# IRComms.net
KiCad netlist of a schematic drawn in Altium Designer
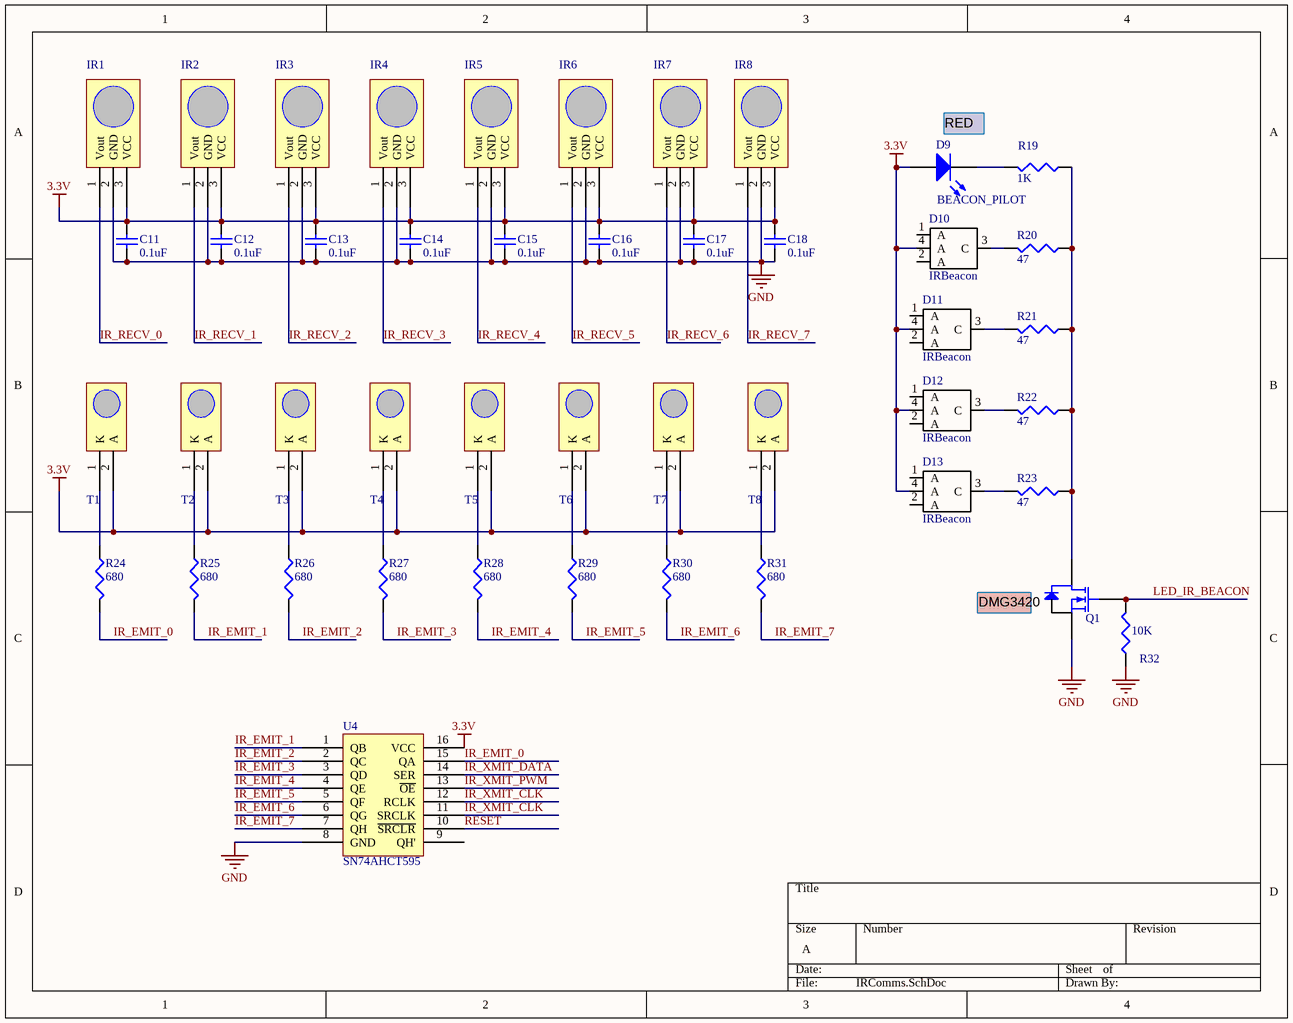
[diagram p0: IRComms.SchDoc]

(export (version "E")
  (design (tool "Eeschema 10.0.6"))
  (components
    (comp (ref "C11")
      (value "0.1uF")
      (footprint "CAPC1005L")
      (description "Capacitor (Semiconductor SIM Model)")
      (fields (field (name "Comment") "Cap Semi") (field (name "PUBLISHER") "Altium Limited"))
      (libsource (lib "Miscellaneous Devices") (part "Cap Semi"))
    )
    (comp (ref "C12")
      (value "0.1uF")
      (footprint "CAPC1005L")
      (description "Capacitor (Semiconductor SIM Model)")
      (fields (field (name "Comment") "Cap Semi") (field (name "PUBLISHER") "Altium Limited"))
      (libsource (lib "Miscellaneous Devices") (part "Cap Semi"))
    )
    (comp (ref "C13")
      (value "0.1uF")
      (footprint "CAPC1005L")
      (description "Capacitor (Semiconductor SIM Model)")
      (fields (field (name "Comment") "Cap Semi") (field (name "PUBLISHER") "Altium Limited"))
      (libsource (lib "Miscellaneous Devices") (part "Cap Semi"))
    )
    (comp (ref "C14")
      (value "0.1uF")
      (footprint "CAPC1005L")
      (description "Capacitor (Semiconductor SIM Model)")
      (fields (field (name "Comment") "Cap Semi") (field (name "PUBLISHER") "Altium Limited"))
      (libsource (lib "Miscellaneous Devices") (part "Cap Semi"))
    )
    (comp (ref "C15")
      (value "0.1uF")
      (footprint "CAPC1005L")
      (description "Capacitor (Semiconductor SIM Model)")
      (fields (field (name "Comment") "Cap Semi") (field (name "PUBLISHER") "Altium Limited"))
      (libsource (lib "Miscellaneous Devices") (part "Cap Semi"))
    )
    (comp (ref "C16")
      (value "0.1uF")
      (footprint "CAPC1005L")
      (description "Capacitor (Semiconductor SIM Model)")
      (fields (field (name "Comment") "Cap Semi") (field (name "PUBLISHER") "Altium Limited"))
      (libsource (lib "Miscellaneous Devices") (part "Cap Semi"))
    )
    (comp (ref "C17")
      (value "0.1uF")
      (footprint "CAPC1005L")
      (description "Capacitor (Semiconductor SIM Model)")
      (fields (field (name "Comment") "Cap Semi") (field (name "PUBLISHER") "Altium Limited"))
      (libsource (lib "Miscellaneous Devices") (part "Cap Semi"))
    )
    (comp (ref "C18")
      (value "0.1uF")
      (footprint "CAPC1005L")
      (description "Capacitor (Semiconductor SIM Model)")
      (fields (field (name "Comment") "Cap Semi") (field (name "PUBLISHER") "Altium Limited"))
      (libsource (lib "Miscellaneous Devices") (part "Cap Semi"))
    )
    (comp (ref "D9")
      (value "BEACON_PILOT")
      (footprint "SurfaceMount(603)")
      (libsource (lib "mrone") (part "LED"))
    )
    (comp (ref "D10") (value "IRBeacon") (footprint "IRBeacon") (libsource (lib "mrone") (part "IRBeacon")))
    (comp (ref "D11") (value "IRBeacon") (footprint "IRBeacon") (libsource (lib "mrone") (part "IRBeacon")))
    (comp (ref "D12") (value "IRBeacon") (footprint "IRBeacon") (libsource (lib "mrone") (part "IRBeacon")))
    (comp (ref "D13") (value "IRBeacon") (footprint "IRBeacon") (libsource (lib "mrone") (part "IRBeacon")))
    (comp (ref "IR1")
      (value "GP1UX31QS")
      (footprint "GP1UX31QS")
      (libsource (lib "mrone") (part "GP1UX31QS"))
    )
    (comp (ref "IR2")
      (value "GP1UX31QS")
      (footprint "GP1UX31QS")
      (libsource (lib "mrone") (part "GP1UX31QS"))
    )
    (comp (ref "IR3")
      (value "GP1UX31QS")
      (footprint "GP1UX31QS")
      (libsource (lib "mrone") (part "GP1UX31QS"))
    )
    (comp (ref "IR4")
      (value "GP1UX31QS")
      (footprint "GP1UX31QS")
      (libsource (lib "mrone") (part "GP1UX31QS"))
    )
    (comp (ref "IR5")
      (value "GP1UX31QS")
      (footprint "GP1UX31QS")
      (libsource (lib "mrone") (part "GP1UX31QS"))
    )
    (comp (ref "IR6")
      (value "GP1UX31QS")
      (footprint "GP1UX31QS")
      (libsource (lib "mrone") (part "GP1UX31QS"))
    )
    (comp (ref "IR7")
      (value "GP1UX31QS")
      (footprint "GP1UX31QS")
      (libsource (lib "mrone") (part "GP1UX31QS"))
    )
    (comp (ref "IR8")
      (value "GP1UX31QS")
      (footprint "GP1UX31QS")
      (libsource (lib "mrone") (part "GP1UX31QS"))
    )
    (comp (ref "Q1") (value "Mosfet") (footprint "SOT-23") (libsource (lib "mrone") (part "Mosfet")))
    (comp (ref "R19")
      (value "1K")
      (footprint "RESC1608L")
      (description "Resistor")
      (fields (field (name "Comment") "Res3") (field (name "PUBLISHER") "Altium Limited"))
      (libsource (lib "Miscellaneous Devices") (part "Res3"))
    )
    (comp (ref "R20")
      (value "47")
      (footprint "RESC1608L")
      (description "Resistor")
      (fields (field (name "Comment") "Res3") (field (name "PUBLISHER") "Altium Limited"))
      (libsource (lib "Miscellaneous Devices") (part "Res3"))
    )
    (comp (ref "R21")
      (value "47")
      (footprint "RESC1608L")
      (description "Resistor")
      (fields (field (name "Comment") "Res3") (field (name "PUBLISHER") "Altium Limited"))
      (libsource (lib "Miscellaneous Devices") (part "Res3"))
    )
    (comp (ref "R22")
      (value "47")
      (footprint "RESC1608L")
      (description "Resistor")
      (fields (field (name "Comment") "Res3") (field (name "PUBLISHER") "Altium Limited"))
      (libsource (lib "Miscellaneous Devices") (part "Res3"))
    )
    (comp (ref "R23")
      (value "47")
      (footprint "RESC1608L")
      (description "Resistor")
      (fields (field (name "Comment") "Res3") (field (name "PUBLISHER") "Altium Limited"))
      (libsource (lib "Miscellaneous Devices") (part "Res3"))
    )
    (comp (ref "R24")
      (value "680")
      (footprint "RESC1608L")
      (description "Resistor")
      (fields (field (name "Comment") "Res3") (field (name "PUBLISHER") "Altium Limited"))
      (libsource (lib "Miscellaneous Devices") (part "Res3"))
    )
    (comp (ref "R25")
      (value "680")
      (footprint "RESC1608L")
      (description "Resistor")
      (fields (field (name "Comment") "Res3") (field (name "PUBLISHER") "Altium Limited"))
      (libsource (lib "Miscellaneous Devices") (part "Res3"))
    )
    (comp (ref "R26")
      (value "680")
      (footprint "RESC1608L")
      (description "Resistor")
      (fields (field (name "Comment") "Res3") (field (name "PUBLISHER") "Altium Limited"))
      (libsource (lib "Miscellaneous Devices") (part "Res3"))
    )
    (comp (ref "R27")
      (value "680")
      (footprint "RESC1608L")
      (description "Resistor")
      (fields (field (name "Comment") "Res3") (field (name "PUBLISHER") "Altium Limited"))
      (libsource (lib "Miscellaneous Devices") (part "Res3"))
    )
    (comp (ref "R28")
      (value "680")
      (footprint "RESC1608L")
      (description "Resistor")
      (fields (field (name "Comment") "Res3") (field (name "PUBLISHER") "Altium Limited"))
      (libsource (lib "Miscellaneous Devices") (part "Res3"))
    )
    (comp (ref "R29")
      (value "680")
      (footprint "RESC1608L")
      (description "Resistor")
      (fields (field (name "Comment") "Res3") (field (name "PUBLISHER") "Altium Limited"))
      (libsource (lib "Miscellaneous Devices") (part "Res3"))
    )
    (comp (ref "R30")
      (value "680")
      (footprint "RESC1608L")
      (description "Resistor")
      (fields (field (name "Comment") "Res3") (field (name "PUBLISHER") "Altium Limited"))
      (libsource (lib "Miscellaneous Devices") (part "Res3"))
    )
    (comp (ref "R31")
      (value "680")
      (footprint "RESC1608L")
      (description "Resistor")
      (fields (field (name "Comment") "Res3") (field (name "PUBLISHER") "Altium Limited"))
      (libsource (lib "Miscellaneous Devices") (part "Res3"))
    )
    (comp (ref "R32")
      (value "10K")
      (footprint "RESC1608L")
      (description "Resistor")
      (fields (field (name "Comment") "Res3") (field (name "PUBLISHER") "Altium Limited"))
      (libsource (lib "Miscellaneous Devices") (part "Res3"))
    )
    (comp (ref "T1") (value "LN54") (footprint "LN54") (libsource (lib "mrone") (part "LN54")))
    (comp (ref "T2") (value "LN54") (footprint "LN54") (libsource (lib "mrone") (part "LN54")))
    (comp (ref "T3") (value "LN54") (footprint "LN54") (libsource (lib "mrone") (part "LN54")))
    (comp (ref "T4") (value "LN54") (footprint "LN54") (libsource (lib "mrone") (part "LN54")))
    (comp (ref "T5") (value "LN54") (footprint "LN54") (libsource (lib "mrone") (part "LN54")))
    (comp (ref "T6") (value "LN54") (footprint "LN54") (libsource (lib "mrone") (part "LN54")))
    (comp (ref "T7") (value "LN54") (footprint "LN54") (libsource (lib "mrone") (part "LN54")))
    (comp (ref "T8") (value "LN54") (footprint "LN54") (libsource (lib "mrone") (part "LN54")))
    (comp (ref "U4")
      (value "SN74AHCT595")
      (footprint "TSSOP-16")
      (description "shift register")
      (libsource (lib "mrone") (part "SN74AHCT595"))
    )
  )
  (nets
    (net (code "1") (name "/IR_EMIT_0") (class "Default")
      (node (ref "R24") (pin "2") (pinfunction "2_2") (pintype "passive"))
      (node (ref "U4") (pin "15") (pinfunction "QA_15") (pintype "passive"))
    )
    (net (code "2") (name "/IR_EMIT_1") (class "Default")
      (node (ref "R25") (pin "2") (pinfunction "2_2") (pintype "passive"))
      (node (ref "U4") (pin "1") (pinfunction "QB_1") (pintype "passive"))
    )
    (net (code "3") (name "/IR_EMIT_2") (class "Default")
      (node (ref "R26") (pin "2") (pinfunction "2_2") (pintype "passive"))
      (node (ref "U4") (pin "2") (pinfunction "QC_2") (pintype "passive"))
    )
    (net (code "4") (name "/IR_EMIT_3") (class "Default")
      (node (ref "R27") (pin "2") (pinfunction "2_2") (pintype "passive"))
      (node (ref "U4") (pin "3") (pinfunction "QD_3") (pintype "passive"))
    )
    (net (code "5") (name "/IR_EMIT_4") (class "Default")
      (node (ref "R28") (pin "2") (pinfunction "2_2") (pintype "passive"))
      (node (ref "U4") (pin "4") (pinfunction "QE_4") (pintype "passive"))
    )
    (net (code "6") (name "/IR_EMIT_5") (class "Default")
      (node (ref "R29") (pin "2") (pinfunction "2_2") (pintype "passive"))
      (node (ref "U4") (pin "5") (pinfunction "QF_5") (pintype "passive"))
    )
    (net (code "7") (name "/IR_EMIT_6") (class "Default")
      (node (ref "R30") (pin "2") (pinfunction "2_2") (pintype "passive"))
      (node (ref "U4") (pin "6") (pinfunction "QG_6") (pintype "passive"))
    )
    (net (code "8") (name "/IR_EMIT_7") (class "Default")
      (node (ref "R31") (pin "2") (pinfunction "2_2") (pintype "passive"))
      (node (ref "U4") (pin "7") (pinfunction "QH_7") (pintype "passive"))
    )
    (net (code "9") (name "/IR_RECV_0") (class "Default")
      (node (ref "IR1") (pin "1") (pinfunction "Vout_1") (pintype "passive"))
    )
    (net (code "10") (name "/IR_RECV_1") (class "Default")
      (node (ref "IR2") (pin "1") (pinfunction "Vout_1") (pintype "passive"))
    )
    (net (code "11") (name "/IR_RECV_2") (class "Default")
      (node (ref "IR3") (pin "1") (pinfunction "Vout_1") (pintype "passive"))
    )
    (net (code "12") (name "/IR_RECV_3") (class "Default")
      (node (ref "IR4") (pin "1") (pinfunction "Vout_1") (pintype "passive"))
    )
    (net (code "13") (name "/IR_RECV_4") (class "Default")
      (node (ref "IR5") (pin "1") (pinfunction "Vout_1") (pintype "passive"))
    )
    (net (code "14") (name "/IR_RECV_5") (class "Default")
      (node (ref "IR6") (pin "1") (pinfunction "Vout_1") (pintype "passive"))
    )
    (net (code "15") (name "/IR_RECV_6") (class "Default")
      (node (ref "IR7") (pin "1") (pinfunction "Vout_1") (pintype "passive"))
    )
    (net (code "16") (name "/IR_RECV_7") (class "Default")
      (node (ref "IR8") (pin "1") (pinfunction "Vout_1") (pintype "passive"))
    )
    (net (code "17") (name "/IR_XMIT_CLK") (class "Default")
      (node (ref "U4") (pin "11") (pinfunction "SRCLK_11") (pintype "passive"))
      (node (ref "U4") (pin "12") (pinfunction "RCLK_12") (pintype "passive"))
    )
    (net (code "18") (name "/IR_XMIT_DATA") (class "Default")
      (node (ref "U4") (pin "14") (pinfunction "SER_14") (pintype "passive"))
    )
    (net (code "19") (name "/IR_XMIT_PWM") (class "Default")
      (node (ref "U4") (pin "13") (pinfunction "~{OE}_13") (pintype "passive"))
    )
    (net (code "20") (name "/LED_IR_BEACON") (class "Default")
      (node (ref "Q1") (pin "1") (pinfunction "G_1") (pintype "passive"))
      (node (ref "R32") (pin "2") (pinfunction "2_2") (pintype "passive"))
    )
    (net (code "21") (name "/RESET") (class "Default")
      (node (ref "U4") (pin "10") (pinfunction "~{SRCLR}_10") (pintype "passive"))
    )
    (net (code "22") (name "3.3V") (class "Default")
      (node (ref "C11") (pin "2") (pinfunction "2_2") (pintype "passive"))
      (node (ref "C12") (pin "2") (pinfunction "2_2") (pintype "passive"))
      (node (ref "C13") (pin "2") (pinfunction "2_2") (pintype "passive"))
      (node (ref "C14") (pin "2") (pinfunction "2_2") (pintype "passive"))
      (node (ref "C15") (pin "2") (pinfunction "2_2") (pintype "passive"))
      (node (ref "C16") (pin "2") (pinfunction "2_2") (pintype "passive"))
      (node (ref "C17") (pin "2") (pinfunction "2_2") (pintype "passive"))
      (node (ref "C18") (pin "2") (pinfunction "2_2") (pintype "passive"))
      (node (ref "D10") (pin "4") (pinfunction "A_4") (pintype "passive"))
      (node (ref "D11") (pin "4") (pinfunction "A_4") (pintype "passive"))
      (node (ref "D12") (pin "4") (pinfunction "A_4") (pintype "passive"))
      (node (ref "D13") (pin "4") (pinfunction "A_4") (pintype "passive"))
      (node (ref "D9") (pin "1") (pinfunction "A_1") (pintype "passive"))
      (node (ref "IR1") (pin "3") (pinfunction "VCC_3") (pintype "power_in"))
      (node (ref "IR2") (pin "3") (pinfunction "VCC_3") (pintype "power_in"))
      (node (ref "IR3") (pin "3") (pinfunction "VCC_3") (pintype "power_in"))
      (node (ref "IR4") (pin "3") (pinfunction "VCC_3") (pintype "power_in"))
      (node (ref "IR5") (pin "3") (pinfunction "VCC_3") (pintype "power_in"))
      (node (ref "IR6") (pin "3") (pinfunction "VCC_3") (pintype "power_in"))
      (node (ref "IR7") (pin "3") (pinfunction "VCC_3") (pintype "power_in"))
      (node (ref "IR8") (pin "3") (pinfunction "VCC_3") (pintype "power_in"))
      (node (ref "T1") (pin "2") (pinfunction "A_2") (pintype "passive"))
      (node (ref "T2") (pin "2") (pinfunction "A_2") (pintype "passive"))
      (node (ref "T3") (pin "2") (pinfunction "A_2") (pintype "passive"))
      (node (ref "T4") (pin "2") (pinfunction "A_2") (pintype "passive"))
      (node (ref "T5") (pin "2") (pinfunction "A_2") (pintype "passive"))
      (node (ref "T6") (pin "2") (pinfunction "A_2") (pintype "passive"))
      (node (ref "T7") (pin "2") (pinfunction "A_2") (pintype "passive"))
      (node (ref "T8") (pin "2") (pinfunction "A_2") (pintype "passive"))
      (node (ref "U4") (pin "16") (pinfunction "VCC_16") (pintype "passive"))
    )
    (net (code "23") (name "GND") (class "Default")
      (node (ref "C11") (pin "1") (pinfunction "1_1") (pintype "passive"))
      (node (ref "C12") (pin "1") (pinfunction "1_1") (pintype "passive"))
      (node (ref "C13") (pin "1") (pinfunction "1_1") (pintype "passive"))
      (node (ref "C14") (pin "1") (pinfunction "1_1") (pintype "passive"))
      (node (ref "C15") (pin "1") (pinfunction "1_1") (pintype "passive"))
      (node (ref "C16") (pin "1") (pinfunction "1_1") (pintype "passive"))
      (node (ref "C17") (pin "1") (pinfunction "1_1") (pintype "passive"))
      (node (ref "C18") (pin "1") (pinfunction "1_1") (pintype "passive"))
      (node (ref "IR1") (pin "2") (pinfunction "GND_2") (pintype "power_in"))
      (node (ref "IR2") (pin "2") (pinfunction "GND_2") (pintype "power_in"))
      (node (ref "IR3") (pin "2") (pinfunction "GND_2") (pintype "power_in"))
      (node (ref "IR4") (pin "2") (pinfunction "GND_2") (pintype "power_in"))
      (node (ref "IR5") (pin "2") (pinfunction "GND_2") (pintype "power_in"))
      (node (ref "IR6") (pin "2") (pinfunction "GND_2") (pintype "power_in"))
      (node (ref "IR7") (pin "2") (pinfunction "GND_2") (pintype "power_in"))
      (node (ref "IR8") (pin "2") (pinfunction "GND_2") (pintype "power_in"))
      (node (ref "Q1") (pin "2") (pinfunction "S_2") (pintype "passive"))
      (node (ref "R32") (pin "1") (pinfunction "1_1") (pintype "passive"))
      (node (ref "U4") (pin "8") (pinfunction "GND_8") (pintype "passive"))
    )
    (net (code "24") (name "Net-(D9-K)") (class "Default")
      (node (ref "D9") (pin "2") (pinfunction "K_2") (pintype "passive"))
      (node (ref "R19") (pin "2") (pinfunction "2_2") (pintype "passive"))
    )
    (net (code "25") (name "Net-(D10-C)") (class "Default")
      (node (ref "D10") (pin "3") (pinfunction "C_3") (pintype "passive"))
      (node (ref "R20") (pin "2") (pinfunction "2_2") (pintype "passive"))
    )
    (net (code "26") (name "Net-(D11-C)") (class "Default")
      (node (ref "D11") (pin "3") (pinfunction "C_3") (pintype "passive"))
      (node (ref "R21") (pin "2") (pinfunction "2_2") (pintype "passive"))
    )
    (net (code "27") (name "Net-(D12-C)") (class "Default")
      (node (ref "D12") (pin "3") (pinfunction "C_3") (pintype "passive"))
      (node (ref "R22") (pin "2") (pinfunction "2_2") (pintype "passive"))
    )
    (net (code "28") (name "Net-(D13-C)") (class "Default")
      (node (ref "D13") (pin "3") (pinfunction "C_3") (pintype "passive"))
      (node (ref "R23") (pin "2") (pinfunction "2_2") (pintype "passive"))
    )
    (net (code "29") (name "Net-(Q1-D)") (class "Default")
      (node (ref "Q1") (pin "3") (pinfunction "D_3") (pintype "passive"))
      (node (ref "R19") (pin "1") (pinfunction "1_1") (pintype "passive"))
      (node (ref "R20") (pin "1") (pinfunction "1_1") (pintype "passive"))
      (node (ref "R21") (pin "1") (pinfunction "1_1") (pintype "passive"))
      (node (ref "R22") (pin "1") (pinfunction "1_1") (pintype "passive"))
      (node (ref "R23") (pin "1") (pinfunction "1_1") (pintype "passive"))
    )
    (net (code "30") (name "Net-(T1-K)") (class "Default")
      (node (ref "R24") (pin "1") (pinfunction "1_1") (pintype "passive"))
      (node (ref "T1") (pin "1") (pinfunction "K_1") (pintype "passive"))
    )
    (net (code "31") (name "Net-(T2-K)") (class "Default")
      (node (ref "R25") (pin "1") (pinfunction "1_1") (pintype "passive"))
      (node (ref "T2") (pin "1") (pinfunction "K_1") (pintype "passive"))
    )
    (net (code "32") (name "Net-(T3-K)") (class "Default")
      (node (ref "R26") (pin "1") (pinfunction "1_1") (pintype "passive"))
      (node (ref "T3") (pin "1") (pinfunction "K_1") (pintype "passive"))
    )
    (net (code "33") (name "Net-(T4-K)") (class "Default")
      (node (ref "R27") (pin "1") (pinfunction "1_1") (pintype "passive"))
      (node (ref "T4") (pin "1") (pinfunction "K_1") (pintype "passive"))
    )
    (net (code "34") (name "Net-(T5-K)") (class "Default")
      (node (ref "R28") (pin "1") (pinfunction "1_1") (pintype "passive"))
      (node (ref "T5") (pin "1") (pinfunction "K_1") (pintype "passive"))
    )
    (net (code "35") (name "Net-(T6-K)") (class "Default")
      (node (ref "R29") (pin "1") (pinfunction "1_1") (pintype "passive"))
      (node (ref "T6") (pin "1") (pinfunction "K_1") (pintype "passive"))
    )
    (net (code "36") (name "Net-(T7-K)") (class "Default")
      (node (ref "R30") (pin "1") (pinfunction "1_1") (pintype "passive"))
      (node (ref "T7") (pin "1") (pinfunction "K_1") (pintype "passive"))
    )
    (net (code "37") (name "Net-(T8-K)") (class "Default")
      (node (ref "R31") (pin "1") (pinfunction "1_1") (pintype "passive"))
      (node (ref "T8") (pin "1") (pinfunction "K_1") (pintype "passive"))
    )
    (net (code "38") (name "unconnected-(D10-A-Pad1)") (class "Default")
      (node (ref "D10") (pin "1") (pinfunction "A_1") (pintype "passive"))
    )
    (net (code "39") (name "unconnected-(D10-A-Pad2)") (class "Default")
      (node (ref "D10") (pin "2") (pinfunction "A_2") (pintype "passive"))
    )
    (net (code "40") (name "unconnected-(D11-A-Pad1)") (class "Default")
      (node (ref "D11") (pin "1") (pinfunction "A_1") (pintype "passive"))
    )
    (net (code "41") (name "unconnected-(D11-A-Pad2)") (class "Default")
      (node (ref "D11") (pin "2") (pinfunction "A_2") (pintype "passive"))
    )
    (net (code "42") (name "unconnected-(D12-A-Pad1)") (class "Default")
      (node (ref "D12") (pin "1") (pinfunction "A_1") (pintype "passive"))
    )
    (net (code "43") (name "unconnected-(D12-A-Pad2)") (class "Default")
      (node (ref "D12") (pin "2") (pinfunction "A_2") (pintype "passive"))
    )
    (net (code "44") (name "unconnected-(D13-A-Pad1)") (class "Default")
      (node (ref "D13") (pin "1") (pinfunction "A_1") (pintype "passive"))
    )
    (net (code "45") (name "unconnected-(D13-A-Pad2)") (class "Default")
      (node (ref "D13") (pin "2") (pinfunction "A_2") (pintype "passive"))
    )
    (net (code "46") (name "unconnected-(U4-QH'-Pad9)") (class "Default")
      (node (ref "U4") (pin "9") (pinfunction "QH'_9") (pintype "passive"))
    )
  )
)
